# USB_MNG_RS.net
KiCad netlist of a schematic drawn in Altium Designer
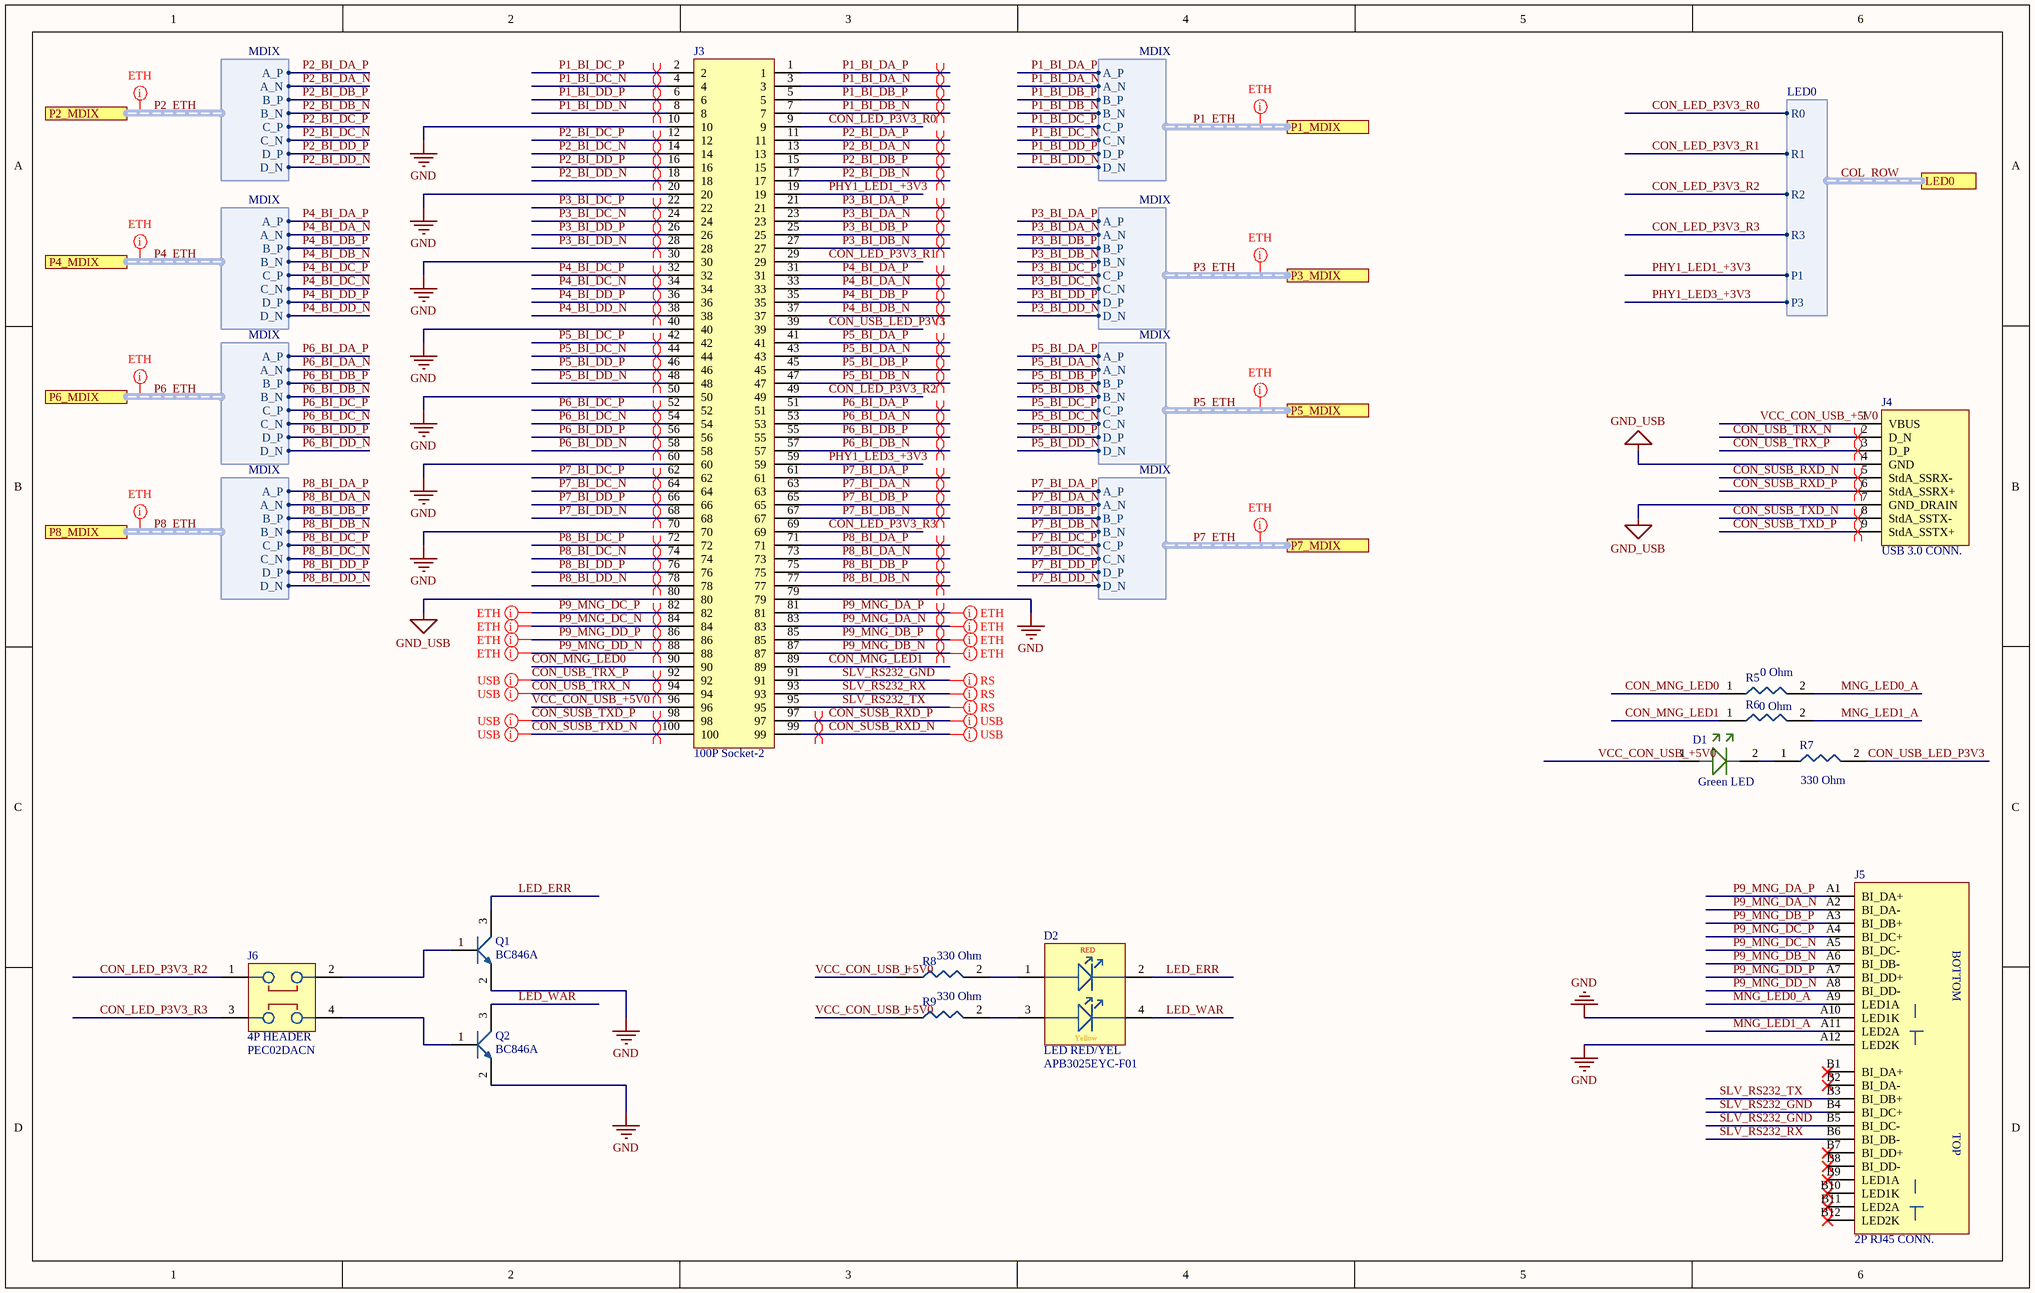
[diagram p0: USB_MNG_RS.SchDoc]

(export (version "E")
  (design (tool "Eeschema 10.0.6"))
  (components
    (comp (ref "D1")
      (value "Green LED")
      (footprint "Green LED")
      (fields (field (name "MANUFACTURER") "Everlight Electronics Co Ltd"))
      (libsource (lib "MyLib") (part "Green LED"))
    )
    (comp (ref "D2")
      (value "LED RED/YEL")
      (footprint "LED RED/YLW")
      (fields (field (name "MANUFACTURER") "Kingbright") (field (name "ORDER NUMBER") "APB3025EYC-F01"))
      (libsource (lib "MyLib") (part "LED RED/YEL"))
    )
    (comp (ref "J3")
      (value "100P Socket-2")
      (footprint "100P SOCKET")
      (description "100P SMD Socket")
      (fields (field (name "MANUFACTURER") "Samtec Inc."))
      (libsource (lib "MyLib") (part "100P Socket-2"))
    )
    (comp (ref "J4")
      (value "USB 3.0 CONN.")
      (footprint "USB 3.0 CONN.")
      (description "USB 3.0 Connector")
      (fields (field (name "MANUFACTURER") "Molex"))
      (libsource (lib "MyLib") (part "USB 3.0 CONN."))
    )
    (comp (ref "J5")
      (value "2P RJ45 CONN.")
      (footprint "2P RJ45 CONN.")
      (fields (field (name "MANUFACTURER") "Würth Elec."))
      (libsource (lib "MyLib") (part "2P RJ45 CONN."))
    )
    (comp (ref "J6")
      (value "4P HEADER")
      (footprint "4P HEADER")
      (description "4 Position Male Header Connector")
      (fields (field (name "MANUFACTURER") "Sullins Conn.") (field (name "ORDER NUMBER") "PEC02DACN"))
      (libsource (lib "MyLib") (part "4P HEADER"))
    )
    (comp (ref "Q1")
      (value "BC846A")
      (footprint "BC846A")
      (fields (field (name "MANUFACTURER") "Fairchild"))
      (libsource (lib "MyLib") (part "BC846A"))
    )
    (comp (ref "Q2")
      (value "BC846A")
      (footprint "BC846A")
      (fields (field (name "MANUFACTURER") "Fairchild"))
      (libsource (lib "MyLib") (part "BC846A"))
    )
    (comp (ref "R5")
      (value "0 Ohm")
      (footprint "0 Ohm Res.")
      (description "0 Ohm Resistor")
      (fields (field (name "MANUFACTURER") "Panasonic") (field (name "Comment") "0 Ohm Res."))
      (libsource (lib "MyLib") (part "0 Ohm Res."))
    )
    (comp (ref "R6")
      (value "0 Ohm")
      (footprint "0 Ohm Res.")
      (description "0 Ohm Resistor")
      (fields (field (name "MANUFACTURER") "Panasonic") (field (name "Comment") "0 Ohm Res."))
      (libsource (lib "MyLib") (part "0 Ohm Res."))
    )
    (comp (ref "R7")
      (value "330 Ohm")
      (footprint "330 Ohm RES.")
      (description "330 Ohm SMD Resistor")
      (fields (field (name "MANUFACTURER") "VISHAY") (field (name "Comment") "330 Ohm RES"))
      (libsource (lib "MyLib") (part "330 Ohm RES"))
    )
    (comp (ref "R8")
      (value "330 Ohm")
      (footprint "330 Ohm RES.")
      (description "330 Ohm SMD Resistor")
      (fields (field (name "MANUFACTURER") "VISHAY") (field (name "Comment") "330 Ohm RES"))
      (libsource (lib "MyLib") (part "330 Ohm RES"))
    )
    (comp (ref "R9")
      (value "330 Ohm")
      (footprint "330 Ohm RES.")
      (description "330 Ohm SMD Resistor")
      (fields (field (name "MANUFACTURER") "VISHAY") (field (name "Comment") "330 Ohm RES"))
      (libsource (lib "MyLib") (part "330 Ohm RES"))
    )
  )
  (nets
    (net (code "11") (name "/CON_LED_P3V3_R0") (class "Default")
      (node (ref "J3") (pin "9") (pinfunction "9_9") (pintype "passive"))
    )
    (net (code "12") (name "/CON_LED_P3V3_R1") (class "Default")
      (node (ref "J3") (pin "29") (pinfunction "29_29") (pintype "passive"))
    )
    (net (code "13") (name "/CON_LED_P3V3_R2") (class "Default")
      (node (ref "J3") (pin "49") (pinfunction "49_49") (pintype "passive"))
      (node (ref "J6") (pin "1") (pinfunction "3_1") (pintype "passive"))
    )
    (net (code "14") (name "/CON_LED_P3V3_R3") (class "Default")
      (node (ref "J3") (pin "69") (pinfunction "69_69") (pintype "passive"))
      (node (ref "J6") (pin "3") (pinfunction "5_3") (pintype "passive"))
    )
    (net (code "15") (name "/CON_MNG_LED0") (class "Default")
      (node (ref "J3") (pin "90") (pinfunction "90_90") (pintype "passive"))
      (node (ref "R5") (pin "1") (pinfunction "1_1") (pintype "passive"))
    )
    (net (code "16") (name "/CON_MNG_LED1") (class "Default")
      (node (ref "J3") (pin "89") (pinfunction "89_89") (pintype "passive"))
      (node (ref "R6") (pin "1") (pinfunction "1_1") (pintype "passive"))
    )
    (net (code "17") (name "/CON_SUSB_RXD_N") (class "Default")
      (node (ref "J3") (pin "99") (pinfunction "99_99") (pintype "passive"))
      (node (ref "J4") (pin "5") (pinfunction "StdA_SSRX-_5") (pintype "passive"))
    )
    (net (code "18") (name "/CON_SUSB_RXD_P") (class "Default")
      (node (ref "J3") (pin "97") (pinfunction "97_97") (pintype "passive"))
      (node (ref "J4") (pin "6") (pinfunction "StdA_SSRX+_6") (pintype "passive"))
    )
    (net (code "19") (name "/CON_SUSB_TXD_N") (class "Default")
      (node (ref "J3") (pin "100") (pinfunction "100_100") (pintype "passive"))
      (node (ref "J4") (pin "8") (pinfunction "StdA_SSTX-_8") (pintype "passive"))
    )
    (net (code "20") (name "/CON_SUSB_TXD_P") (class "Default")
      (node (ref "J3") (pin "98") (pinfunction "98_98") (pintype "passive"))
      (node (ref "J4") (pin "9") (pinfunction "StdA_SSTX+_9") (pintype "passive"))
    )
    (net (code "21") (name "/CON_USB_LED_P3V3") (class "Default")
      (node (ref "J3") (pin "39") (pinfunction "39_39") (pintype "passive"))
      (node (ref "R7") (pin "2") (pinfunction "2_2") (pintype "passive"))
    )
    (net (code "22") (name "/CON_USB_TRX_N") (class "Default")
      (node (ref "J3") (pin "94") (pinfunction "94_94") (pintype "passive"))
      (node (ref "J4") (pin "2") (pinfunction "D_N_2") (pintype "passive"))
    )
    (net (code "23") (name "/CON_USB_TRX_P") (class "Default")
      (node (ref "J3") (pin "92") (pinfunction "92_92") (pintype "passive"))
      (node (ref "J4") (pin "3") (pinfunction "D_P_3") (pintype "passive"))
    )
    (net (code "24") (name "/LED_ERR") (class "Default")
      (node (ref "D2") (pin "2") (pinfunction "7_2") (pintype "passive"))
      (node (ref "Q1") (pin "3") (pinfunction "2_3") (pintype "passive"))
    )
    (net (code "25") (name "/LED_WAR") (class "Default")
      (node (ref "D2") (pin "4") (pinfunction "9_4") (pintype "passive"))
      (node (ref "Q2") (pin "3") (pinfunction "2_3") (pintype "passive"))
    )
    (net (code "26") (name "/MNG_LED0_A") (class "Default")
      (node (ref "J5") (pin "A9") (pinfunction "LED1A_A9") (pintype "passive"))
      (node (ref "R5") (pin "2") (pinfunction "2_2") (pintype "passive"))
    )
    (net (code "27") (name "/MNG_LED1_A") (class "Default")
      (node (ref "J5") (pin "A11") (pinfunction "LED2A_A11") (pintype "passive"))
      (node (ref "R6") (pin "2") (pinfunction "2_2") (pintype "passive"))
    )
    (net (code "28") (name "/P1_BI_DA_N") (class "Default")
      (node (ref "J3") (pin "3") (pinfunction "3_3") (pintype "passive"))
    )
    (net (code "29") (name "/P1_BI_DA_P") (class "Default")
      (node (ref "J3") (pin "1") (pinfunction "1_1") (pintype "passive"))
    )
    (net (code "30") (name "/P1_BI_DB_N") (class "Default")
      (node (ref "J3") (pin "7") (pinfunction "7_7") (pintype "passive"))
    )
    (net (code "31") (name "/P1_BI_DB_P") (class "Default")
      (node (ref "J3") (pin "5") (pinfunction "5_5") (pintype "passive"))
    )
    (net (code "32") (name "/P1_BI_DC_N") (class "Default")
      (node (ref "J3") (pin "4") (pinfunction "4_4") (pintype "passive"))
    )
    (net (code "33") (name "/P1_BI_DC_P") (class "Default")
      (node (ref "J3") (pin "2") (pinfunction "2_2") (pintype "passive"))
    )
    (net (code "34") (name "/P1_BI_DD_N") (class "Default")
      (node (ref "J3") (pin "8") (pinfunction "8_8") (pintype "passive"))
    )
    (net (code "35") (name "/P1_BI_DD_P") (class "Default")
      (node (ref "J3") (pin "6") (pinfunction "6_6") (pintype "passive"))
    )
    (net (code "37") (name "/P2_BI_DA_N") (class "Default")
      (node (ref "J3") (pin "13") (pinfunction "13_13") (pintype "passive"))
    )
    (net (code "38") (name "/P2_BI_DA_P") (class "Default")
      (node (ref "J3") (pin "11") (pinfunction "11_11") (pintype "passive"))
    )
    (net (code "39") (name "/P2_BI_DB_N") (class "Default")
      (node (ref "J3") (pin "17") (pinfunction "17_17") (pintype "passive"))
    )
    (net (code "40") (name "/P2_BI_DB_P") (class "Default")
      (node (ref "J3") (pin "15") (pinfunction "15_15") (pintype "passive"))
    )
    (net (code "41") (name "/P2_BI_DC_N") (class "Default")
      (node (ref "J3") (pin "14") (pinfunction "14_14") (pintype "passive"))
    )
    (net (code "42") (name "/P2_BI_DC_P") (class "Default")
      (node (ref "J3") (pin "12") (pinfunction "12_12") (pintype "passive"))
    )
    (net (code "43") (name "/P2_BI_DD_N") (class "Default")
      (node (ref "J3") (pin "18") (pinfunction "18_18") (pintype "passive"))
    )
    (net (code "44") (name "/P2_BI_DD_P") (class "Default")
      (node (ref "J3") (pin "16") (pinfunction "16_16") (pintype "passive"))
    )
    (net (code "46") (name "/P3_BI_DA_N") (class "Default")
      (node (ref "J3") (pin "23") (pinfunction "23_23") (pintype "passive"))
    )
    (net (code "47") (name "/P3_BI_DA_P") (class "Default")
      (node (ref "J3") (pin "21") (pinfunction "21_21") (pintype "passive"))
    )
    (net (code "48") (name "/P3_BI_DB_N") (class "Default")
      (node (ref "J3") (pin "27") (pinfunction "27_27") (pintype "passive"))
    )
    (net (code "49") (name "/P3_BI_DB_P") (class "Default")
      (node (ref "J3") (pin "25") (pinfunction "25_25") (pintype "passive"))
    )
    (net (code "50") (name "/P3_BI_DC_N") (class "Default")
      (node (ref "J3") (pin "24") (pinfunction "24_24") (pintype "passive"))
    )
    (net (code "51") (name "/P3_BI_DC_P") (class "Default")
      (node (ref "J3") (pin "22") (pinfunction "22_22") (pintype "passive"))
    )
    (net (code "52") (name "/P3_BI_DD_N") (class "Default")
      (node (ref "J3") (pin "28") (pinfunction "28_28") (pintype "passive"))
    )
    (net (code "53") (name "/P3_BI_DD_P") (class "Default")
      (node (ref "J3") (pin "26") (pinfunction "26_26") (pintype "passive"))
    )
    (net (code "55") (name "/P4_BI_DA_N") (class "Default")
      (node (ref "J3") (pin "33") (pinfunction "33_33") (pintype "passive"))
    )
    (net (code "56") (name "/P4_BI_DA_P") (class "Default")
      (node (ref "J3") (pin "31") (pinfunction "31_31") (pintype "passive"))
    )
    (net (code "57") (name "/P4_BI_DB_N") (class "Default")
      (node (ref "J3") (pin "37") (pinfunction "37_37") (pintype "passive"))
    )
    (net (code "58") (name "/P4_BI_DB_P") (class "Default")
      (node (ref "J3") (pin "35") (pinfunction "35_35") (pintype "passive"))
    )
    (net (code "59") (name "/P4_BI_DC_N") (class "Default")
      (node (ref "J3") (pin "34") (pinfunction "34_34") (pintype "passive"))
    )
    (net (code "60") (name "/P4_BI_DC_P") (class "Default")
      (node (ref "J3") (pin "32") (pinfunction "32_32") (pintype "passive"))
    )
    (net (code "61") (name "/P4_BI_DD_N") (class "Default")
      (node (ref "J3") (pin "38") (pinfunction "38_38") (pintype "passive"))
    )
    (net (code "62") (name "/P4_BI_DD_P") (class "Default")
      (node (ref "J3") (pin "36") (pinfunction "36_36") (pintype "passive"))
    )
    (net (code "64") (name "/P5_BI_DA_N") (class "Default")
      (node (ref "J3") (pin "43") (pinfunction "43_43") (pintype "passive"))
    )
    (net (code "65") (name "/P5_BI_DA_P") (class "Default")
      (node (ref "J3") (pin "41") (pinfunction "41_41") (pintype "passive"))
    )
    (net (code "66") (name "/P5_BI_DB_N") (class "Default")
      (node (ref "J3") (pin "47") (pinfunction "47_47") (pintype "passive"))
    )
    (net (code "67") (name "/P5_BI_DB_P") (class "Default")
      (node (ref "J3") (pin "45") (pinfunction "45_45") (pintype "passive"))
    )
    (net (code "68") (name "/P5_BI_DC_N") (class "Default")
      (node (ref "J3") (pin "44") (pinfunction "44_44") (pintype "passive"))
    )
    (net (code "69") (name "/P5_BI_DC_P") (class "Default")
      (node (ref "J3") (pin "42") (pinfunction "42_42") (pintype "passive"))
    )
    (net (code "70") (name "/P5_BI_DD_N") (class "Default")
      (node (ref "J3") (pin "48") (pinfunction "48_48") (pintype "passive"))
    )
    (net (code "71") (name "/P5_BI_DD_P") (class "Default")
      (node (ref "J3") (pin "46") (pinfunction "46_46") (pintype "passive"))
    )
    (net (code "73") (name "/P6_BI_DA_N") (class "Default")
      (node (ref "J3") (pin "53") (pinfunction "53_53") (pintype "passive"))
    )
    (net (code "74") (name "/P6_BI_DA_P") (class "Default")
      (node (ref "J3") (pin "51") (pinfunction "51_51") (pintype "passive"))
    )
    (net (code "75") (name "/P6_BI_DB_N") (class "Default")
      (node (ref "J3") (pin "57") (pinfunction "57_57") (pintype "passive"))
    )
    (net (code "76") (name "/P6_BI_DB_P") (class "Default")
      (node (ref "J3") (pin "55") (pinfunction "55_55") (pintype "passive"))
    )
    (net (code "77") (name "/P6_BI_DC_N") (class "Default")
      (node (ref "J3") (pin "54") (pinfunction "54_54") (pintype "passive"))
    )
    (net (code "78") (name "/P6_BI_DC_P") (class "Default")
      (node (ref "J3") (pin "52") (pinfunction "52_52") (pintype "passive"))
    )
    (net (code "79") (name "/P6_BI_DD_N") (class "Default")
      (node (ref "J3") (pin "58") (pinfunction "58_58") (pintype "passive"))
    )
    (net (code "80") (name "/P6_BI_DD_P") (class "Default")
      (node (ref "J3") (pin "56") (pinfunction "56_56") (pintype "passive"))
    )
    (net (code "82") (name "/P7_BI_DA_N") (class "Default")
      (node (ref "J3") (pin "63") (pinfunction "63_63") (pintype "passive"))
    )
    (net (code "83") (name "/P7_BI_DA_P") (class "Default")
      (node (ref "J3") (pin "61") (pinfunction "61_61") (pintype "passive"))
    )
    (net (code "84") (name "/P7_BI_DB_N") (class "Default")
      (node (ref "J3") (pin "67") (pinfunction "67_67") (pintype "passive"))
    )
    (net (code "85") (name "/P7_BI_DB_P") (class "Default")
      (node (ref "J3") (pin "65") (pinfunction "65_65") (pintype "passive"))
    )
    (net (code "86") (name "/P7_BI_DC_N") (class "Default")
      (node (ref "J3") (pin "64") (pinfunction "64_64") (pintype "passive"))
    )
    (net (code "87") (name "/P7_BI_DC_P") (class "Default")
      (node (ref "J3") (pin "62") (pinfunction "62_62") (pintype "passive"))
    )
    (net (code "88") (name "/P7_BI_DD_N") (class "Default")
      (node (ref "J3") (pin "68") (pinfunction "68_68") (pintype "passive"))
    )
    (net (code "89") (name "/P7_BI_DD_P") (class "Default")
      (node (ref "J3") (pin "66") (pinfunction "66_66") (pintype "passive"))
    )
    (net (code "91") (name "/P8_BI_DA_N") (class "Default")
      (node (ref "J3") (pin "73") (pinfunction "73_73") (pintype "passive"))
    )
    (net (code "92") (name "/P8_BI_DA_P") (class "Default")
      (node (ref "J3") (pin "71") (pinfunction "71_71") (pintype "passive"))
    )
    (net (code "93") (name "/P8_BI_DB_N") (class "Default")
      (node (ref "J3") (pin "77") (pinfunction "77_77") (pintype "passive"))
    )
    (net (code "94") (name "/P8_BI_DB_P") (class "Default")
      (node (ref "J3") (pin "75") (pinfunction "75_75") (pintype "passive"))
    )
    (net (code "95") (name "/P8_BI_DC_N") (class "Default")
      (node (ref "J3") (pin "74") (pinfunction "74_74") (pintype "passive"))
    )
    (net (code "96") (name "/P8_BI_DC_P") (class "Default")
      (node (ref "J3") (pin "72") (pinfunction "72_72") (pintype "passive"))
    )
    (net (code "97") (name "/P8_BI_DD_N") (class "Default")
      (node (ref "J3") (pin "78") (pinfunction "78_78") (pintype "passive"))
    )
    (net (code "98") (name "/P8_BI_DD_P") (class "Default")
      (node (ref "J3") (pin "76") (pinfunction "76_76") (pintype "passive"))
    )
    (net (code "100") (name "/P9_MNG_DA_N") (class "Default")
      (node (ref "J3") (pin "83") (pinfunction "83_83") (pintype "passive"))
      (node (ref "J5") (pin "A2") (pinfunction "BI_DA-_A2") (pintype "passive"))
    )
    (net (code "101") (name "/P9_MNG_DA_P") (class "Default")
      (node (ref "J3") (pin "81") (pinfunction "81_81") (pintype "passive"))
      (node (ref "J5") (pin "A1") (pinfunction "BI_DA+_A1") (pintype "passive"))
    )
    (net (code "102") (name "/P9_MNG_DB_N") (class "Default")
      (node (ref "J3") (pin "87") (pinfunction "87_87") (pintype "passive"))
      (node (ref "J5") (pin "A6") (pinfunction "BI_DB-_A6") (pintype "passive"))
    )
    (net (code "103") (name "/P9_MNG_DB_P") (class "Default")
      (node (ref "J3") (pin "85") (pinfunction "85_85") (pintype "passive"))
      (node (ref "J5") (pin "A3") (pinfunction "BI_DB+_A3") (pintype "passive"))
    )
    (net (code "104") (name "/P9_MNG_DC_N") (class "Default")
      (node (ref "J3") (pin "84") (pinfunction "84_84") (pintype "passive"))
      (node (ref "J5") (pin "A5") (pinfunction "BI_DC-_A5") (pintype "passive"))
    )
    (net (code "105") (name "/P9_MNG_DC_P") (class "Default")
      (node (ref "J3") (pin "82") (pinfunction "82_82") (pintype "passive"))
      (node (ref "J5") (pin "A4") (pinfunction "BI_DC+_A4") (pintype "passive"))
    )
    (net (code "106") (name "/P9_MNG_DD_N") (class "Default")
      (node (ref "J3") (pin "88") (pinfunction "88_88") (pintype "passive"))
      (node (ref "J5") (pin "A8") (pinfunction "BI_DD-_A8") (pintype "passive"))
    )
    (net (code "107") (name "/P9_MNG_DD_P") (class "Default")
      (node (ref "J3") (pin "86") (pinfunction "86_86") (pintype "passive"))
      (node (ref "J5") (pin "A7") (pinfunction "BI_DD+_A7") (pintype "passive"))
    )
    (net (code "108") (name "/PHY1_LED1_+3V3") (class "Default")
      (node (ref "J3") (pin "19") (pinfunction "19_19") (pintype "passive"))
    )
    (net (code "109") (name "/PHY1_LED3_+3V3") (class "Default")
      (node (ref "J3") (pin "59") (pinfunction "59_59") (pintype "passive"))
    )
    (net (code "110") (name "/SLV_RS232_GND") (class "Default")
      (node (ref "J3") (pin "91") (pinfunction "91_91") (pintype "passive"))
      (node (ref "J5") (pin "B4") (pinfunction "BI_DC+_B4") (pintype "passive"))
      (node (ref "J5") (pin "B5") (pinfunction "BI_DC-_B5") (pintype "passive"))
    )
    (net (code "111") (name "/SLV_RS232_RX") (class "Default")
      (node (ref "J3") (pin "93") (pinfunction "93_93") (pintype "passive"))
      (node (ref "J5") (pin "B6") (pinfunction "BI_DB-_B6") (pintype "passive"))
    )
    (net (code "112") (name "/SLV_RS232_TX") (class "Default")
      (node (ref "J3") (pin "95") (pinfunction "95_95") (pintype "passive"))
      (node (ref "J5") (pin "B3") (pinfunction "BI_DB+_B3") (pintype "passive"))
    )
    (net (code "113") (name "/VCC_CON_USB_+5V0") (class "Default")
      (node (ref "D1") (pin "1") (pinfunction "PVCC_1") (pintype "passive"))
      (node (ref "J3") (pin "96") (pinfunction "96_96") (pintype "passive"))
      (node (ref "J4") (pin "1") (pinfunction "VBUS_1") (pintype "passive"))
      (node (ref "R8") (pin "1") (pinfunction "1_1") (pintype "passive"))
      (node (ref "R9") (pin "1") (pinfunction "1_1") (pintype "passive"))
    )
    (net (code "114") (name "GND") (class "Default")
      (node (ref "J3") (pin "10") (pinfunction "10_10") (pintype "passive"))
      (node (ref "J3") (pin "20") (pinfunction "20_20") (pintype "passive"))
      (node (ref "J3") (pin "30") (pinfunction "30_30") (pintype "passive"))
      (node (ref "J3") (pin "40") (pinfunction "40_40") (pintype "passive"))
      (node (ref "J3") (pin "50") (pinfunction "50_50") (pintype "passive"))
      (node (ref "J3") (pin "60") (pinfunction "60_60") (pintype "passive"))
      (node (ref "J3") (pin "70") (pinfunction "70_70") (pintype "passive"))
      (node (ref "J3") (pin "79") (pinfunction "79_79") (pintype "passive"))
      (node (ref "J5") (pin "A10") (pinfunction "LED1K_A10") (pintype "passive"))
      (node (ref "J5") (pin "A12") (pinfunction "LED2K_A12") (pintype "passive"))
      (node (ref "Q1") (pin "2") (pinfunction "1_2") (pintype "passive"))
      (node (ref "Q2") (pin "2") (pinfunction "1_2") (pintype "passive"))
    )
    (net (code "115") (name "GND_USB") (class "Default")
      (node (ref "J3") (pin "80") (pinfunction "80_80") (pintype "passive"))
      (node (ref "J4") (pin "4") (pinfunction "GND_4") (pintype "passive"))
      (node (ref "J4") (pin "7") (pinfunction "GND_DRAIN_7") (pintype "passive"))
    )
    (net (code "116") (name "Net-(D1-PVCC-Pad2)") (class "Default")
      (node (ref "D1") (pin "2") (pinfunction "PVCC_2") (pintype "passive"))
      (node (ref "R7") (pin "1") (pinfunction "1_1") (pintype "passive"))
    )
    (net (code "117") (name "Net-(D2-6)") (class "Default")
      (node (ref "D2") (pin "1") (pinfunction "6_1") (pintype "passive"))
      (node (ref "R8") (pin "2") (pinfunction "2_2") (pintype "passive"))
    )
    (net (code "118") (name "Net-(D2-8)") (class "Default")
      (node (ref "D2") (pin "3") (pinfunction "8_3") (pintype "passive"))
      (node (ref "R9") (pin "2") (pinfunction "2_2") (pintype "passive"))
    )
    (net (code "119") (name "Net-(J6-4)") (class "Default")
      (node (ref "J6") (pin "2") (pinfunction "4_2") (pintype "passive"))
      (node (ref "Q1") (pin "1") (pinfunction "0_1") (pintype "passive"))
    )
    (net (code "120") (name "Net-(J6-6)") (class "Default")
      (node (ref "J6") (pin "4") (pinfunction "6_4") (pintype "passive"))
      (node (ref "Q2") (pin "1") (pinfunction "0_1") (pintype "passive"))
    )
    (net (code "121") (name "unconnected-(J5-BI_DA+-PadB1)") (class "Default")
      (node (ref "J5") (pin "B1") (pinfunction "BI_DA+_B1") (pintype "passive+no_connect"))
    )
    (net (code "122") (name "unconnected-(J5-BI_DA--PadB2)") (class "Default")
      (node (ref "J5") (pin "B2") (pinfunction "BI_DA-_B2") (pintype "passive+no_connect"))
    )
    (net (code "123") (name "unconnected-(J5-BI_DD+-PadB7)") (class "Default")
      (node (ref "J5") (pin "B7") (pinfunction "BI_DD+_B7") (pintype "passive+no_connect"))
    )
    (net (code "124") (name "unconnected-(J5-BI_DD--PadB8)") (class "Default")
      (node (ref "J5") (pin "B8") (pinfunction "BI_DD-_B8") (pintype "passive+no_connect"))
    )
    (net (code "125") (name "unconnected-(J5-LED1A-PadB9)") (class "Default")
      (node (ref "J5") (pin "B9") (pinfunction "LED1A_B9") (pintype "passive+no_connect"))
    )
    (net (code "126") (name "unconnected-(J5-LED1K-PadB10)") (class "Default")
      (node (ref "J5") (pin "B10") (pinfunction "LED1K_B10") (pintype "passive+no_connect"))
    )
    (net (code "127") (name "unconnected-(J5-LED2A-PadB11)") (class "Default")
      (node (ref "J5") (pin "B11") (pinfunction "LED2A_B11") (pintype "passive+no_connect"))
    )
    (net (code "128") (name "unconnected-(J5-LED2K-PadB12)") (class "Default")
      (node (ref "J5") (pin "B12") (pinfunction "LED2K_B12") (pintype "passive+no_connect"))
    )
  )
)
